# Nano-CC-EL_0v6_2_ENP252-17.net
KiCad netlist of a schematic drawn in EAGLE
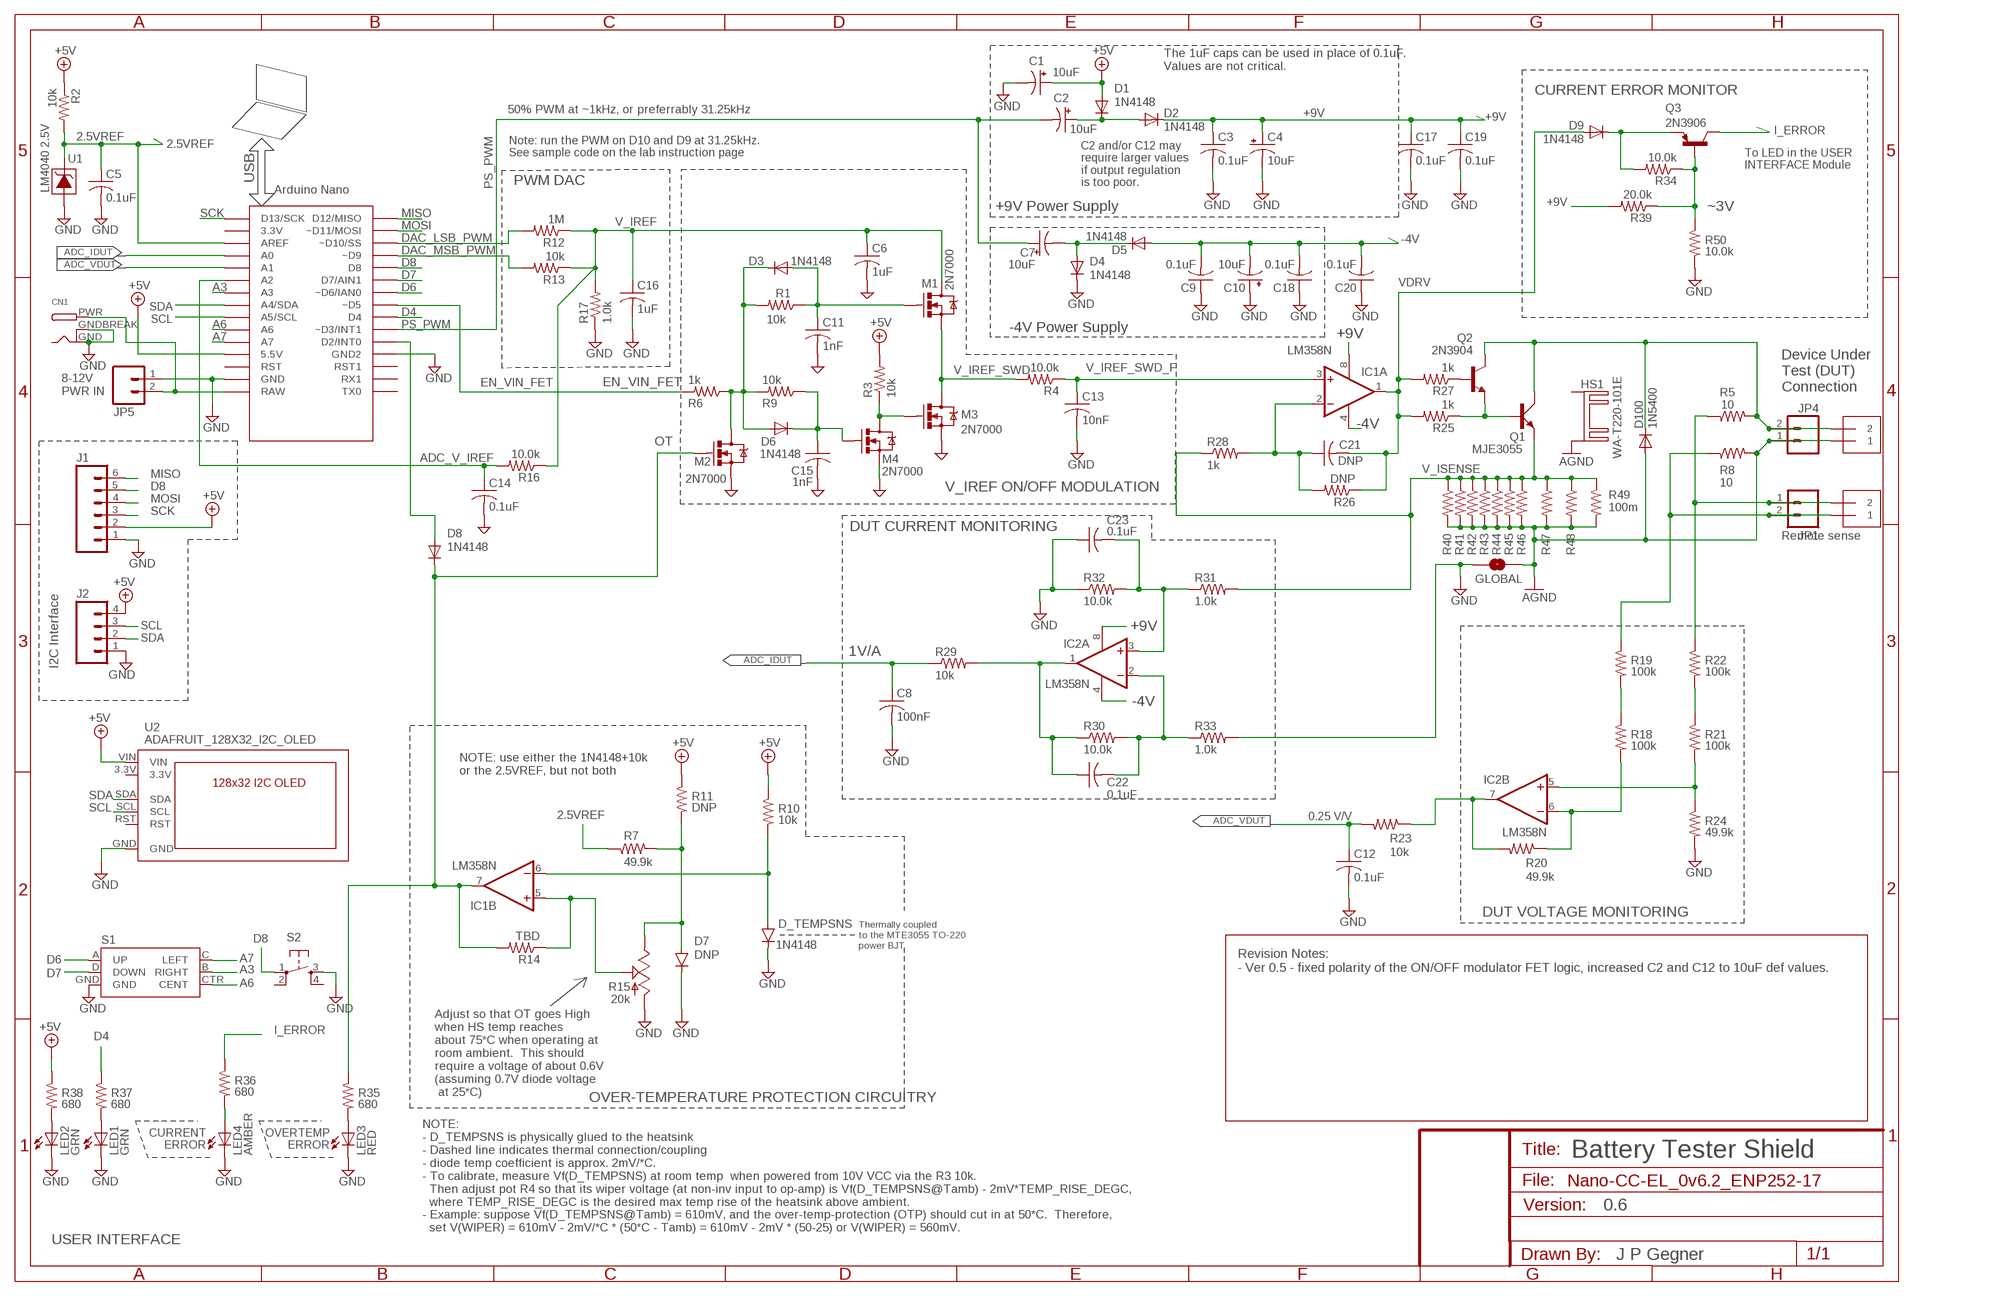
[diagram p0: schematic, sheet 1]

(export (version "E")
  (design (tool "Eeschema 10.0.6"))
  (components
    (comp (ref "C1")
      (value "10uF")
      (footprint "eagle-import:E5-5")
      (libsource (lib "eagle-import") (part "CPOL-USE5-5"))
    )
    (comp (ref "C2")
      (value "10uF")
      (footprint "eagle-import:E5-5")
      (libsource (lib "eagle-import") (part "CPOL-USE5-5"))
    )
    (comp (ref "C3")
      (value "0.1uF")
      (footprint "eagle-import:C025-025X050")
      (libsource (lib "eagle-import") (part "C-US025-025X050"))
    )
    (comp (ref "C4")
      (value "10uF")
      (footprint "eagle-import:E5-5")
      (libsource (lib "eagle-import") (part "CPOL-USE5-5"))
    )
    (comp (ref "C5")
      (value "0.1uF")
      (footprint "eagle-import:C025-025X050")
      (libsource (lib "eagle-import") (part "C-US025-025X050"))
    )
    (comp (ref "C6")
      (value "1uF")
      (footprint "eagle-import:C025-025X050")
      (libsource (lib "eagle-import") (part "C-US025-025X050"))
    )
    (comp (ref "C7")
      (value "10uF")
      (footprint "eagle-import:E5-5")
      (libsource (lib "eagle-import") (part "CPOL-USE5-5"))
    )
    (comp (ref "C8")
      (value "100nF")
      (footprint "eagle-import:C025-024X044")
      (libsource (lib "eagle-import") (part "C-US025-024X044"))
    )
    (comp (ref "C9")
      (value "0.1uF")
      (footprint "eagle-import:C025-025X050")
      (libsource (lib "eagle-import") (part "C-US025-025X050"))
    )
    (comp (ref "C10")
      (value "10uF")
      (footprint "eagle-import:E5-5")
      (libsource (lib "eagle-import") (part "CPOL-USE5-5"))
    )
    (comp (ref "C11")
      (value "1nF")
      (footprint "eagle-import:C025-025X050")
      (libsource (lib "eagle-import") (part "C-US025-025X050"))
    )
    (comp (ref "C12")
      (value "0.1uF")
      (footprint "eagle-import:C025-025X050")
      (libsource (lib "eagle-import") (part "C-US025-025X050"))
    )
    (comp (ref "C13")
      (value "10nF")
      (footprint "eagle-import:C025-025X050")
      (libsource (lib "eagle-import") (part "C-US025-025X050"))
    )
    (comp (ref "C14")
      (value "0.1uF")
      (footprint "eagle-import:C025-025X050")
      (libsource (lib "eagle-import") (part "C-US025-025X050"))
    )
    (comp (ref "C15")
      (value "1nF")
      (footprint "eagle-import:C025-025X050")
      (libsource (lib "eagle-import") (part "C-US025-025X050"))
    )
    (comp (ref "C16")
      (value "1uF")
      (footprint "eagle-import:C025-025X050")
      (libsource (lib "eagle-import") (part "C-US025-025X050"))
    )
    (comp (ref "C17")
      (value "0.1uF")
      (footprint "eagle-import:C025-025X050")
      (libsource (lib "eagle-import") (part "C-US025-025X050"))
    )
    (comp (ref "C18")
      (value "0.1uF")
      (footprint "eagle-import:C025-025X050")
      (libsource (lib "eagle-import") (part "C-US025-025X050"))
    )
    (comp (ref "C19")
      (value "0.1uF")
      (footprint "eagle-import:C025-025X050")
      (libsource (lib "eagle-import") (part "C-US025-025X050"))
    )
    (comp (ref "C20")
      (value "0.1uF")
      (footprint "eagle-import:C025-025X050")
      (libsource (lib "eagle-import") (part "C-US025-025X050"))
    )
    (comp (ref "C21")
      (value "DNP")
      (footprint "eagle-import:C025-025X050")
      (libsource (lib "eagle-import") (part "C-US025-025X050"))
    )
    (comp (ref "C22")
      (value "0.1uF")
      (footprint "eagle-import:C025-025X050")
      (libsource (lib "eagle-import") (part "C-US025-025X050"))
    )
    (comp (ref "C23")
      (value "0.1uF")
      (footprint "eagle-import:C025-025X050")
      (libsource (lib "eagle-import") (part "C-US025-025X050"))
    )
    (comp (ref "CN1")
      (value "DCBARRELPTH")
      (footprint "eagle-import:DCJACK_2MM_PTH")
      (libsource (lib "eagle-import") (part "DCBARRELPTH"))
    )
    (comp (ref "D1")
      (value "1N4148")
      (footprint "eagle-import:0207_2V-D")
      (libsource (lib "eagle-import") (part "1N4148"))
    )
    (comp (ref "D2")
      (value "1N4148")
      (footprint "eagle-import:0207_2V-D")
      (libsource (lib "eagle-import") (part "1N4148"))
    )
    (comp (ref "D3")
      (value "1N4148")
      (footprint "eagle-import:0207_2V-D")
      (libsource (lib "eagle-import") (part "1N4148"))
    )
    (comp (ref "D4")
      (value "1N4148")
      (footprint "eagle-import:0207_2V-D")
      (libsource (lib "eagle-import") (part "1N4148"))
    )
    (comp (ref "D5")
      (value "1N4148")
      (footprint "eagle-import:0207_2V-D")
      (libsource (lib "eagle-import") (part "1N4148"))
    )
    (comp (ref "D6")
      (value "1N4148")
      (footprint "eagle-import:0207_2V-D")
      (libsource (lib "eagle-import") (part "1N4148"))
    )
    (comp (ref "D7")
      (value "DNP")
      (footprint "eagle-import:0207_2V-D")
      (libsource (lib "eagle-import") (part "ideal_elements_1N4148"))
    )
    (comp (ref "D8")
      (value "1N4148")
      (footprint "eagle-import:0207_2V-D")
      (libsource (lib "eagle-import") (part "1N4148"))
    )
    (comp (ref "D9")
      (value "1N4148")
      (footprint "eagle-import:0207_2V-D")
      (libsource (lib "eagle-import") (part "1N4148"))
    )
    (comp (ref "D100")
      (value "1N5400")
      (footprint "eagle-import:DO201-15")
      (libsource (lib "eagle-import") (part "1N5400"))
    )
    (comp (ref "D_TEMPSNS")
      (value "1N4148")
      (footprint "eagle-import:0207_2V-D")
      (libsource (lib "eagle-import") (part "ideal_elements_1N4148"))
    )
    (comp (ref "GLOBAL")
      (value "JUMPER-PAD-2-NC_BY_TRACENO_SILK")
      (footprint "eagle-import:PAD-JUMPER-2-NC_BY_TRACE_NO_SILK")
      (libsource (lib "eagle-import") (part "JUMPER-PAD-2-NC_BY_TRACENO_SILK"))
    )
    (comp (ref "HS1")
      (value "WA-T220-101E")
      (footprint "eagle-import:WX-T220-101E")
      (libsource (lib "eagle-import") (part "WA-T220-101E"))
    )
    (comp (ref "IC1")
      (value "LM358N")
      (footprint "eagle-import:DIL08")
      (libsource (lib "eagle-import") (part "LM358N"))
    )
    (comp (ref "IC2")
      (value "LM358N")
      (footprint "eagle-import:DIL08")
      (libsource (lib "eagle-import") (part "LM358N"))
    )
    (comp (ref "J1")
      (value "M06POLAR")
      (footprint "eagle-import:MOLEX-1X6")
      (libsource (lib "eagle-import") (part "M06POLAR"))
    )
    (comp (ref "J2")
      (value "M04LOCK_LONGPADS")
      (footprint "eagle-import:1X04_LOCK_LONGPADS")
      (libsource (lib "eagle-import") (part "M04LOCK_LONGPADS"))
    )
    (comp (ref "JP1")
      (value "M02PTH")
      (footprint "eagle-import:1X02")
      (libsource (lib "eagle-import") (part "M02PTH"))
    )
    (comp (ref "JP2")
      (value "1X2-3.5MM")
      (footprint "eagle-import:1X2-3.5MM")
      (libsource (lib "eagle-import") (part "1X2-3.5MM"))
    )
    (comp (ref "JP3")
      (value "1X2-3.5MM")
      (footprint "eagle-import:1X2-3.5MM")
      (libsource (lib "eagle-import") (part "1X2-3.5MM"))
    )
    (comp (ref "JP4")
      (value "M02PTH")
      (footprint "eagle-import:1X02")
      (libsource (lib "eagle-import") (part "M02PTH"))
    )
    (comp (ref "JP5")
      (value "M02PTH")
      (footprint "eagle-import:1X02")
      (libsource (lib "eagle-import") (part "M02PTH"))
    )
    (comp (ref "LED1")
      (value "GRN")
      (footprint "eagle-import:LED3MM-NS")
      (libsource (lib "eagle-import") (part "LED-3MM-NO_SILK"))
    )
    (comp (ref "LED2")
      (value "GRN")
      (footprint "eagle-import:LED3MM-NS")
      (libsource (lib "eagle-import") (part "LED-3MM-NO_SILK"))
    )
    (comp (ref "LED3")
      (value "RED")
      (footprint "eagle-import:LED3MM-NS")
      (libsource (lib "eagle-import") (part "LED-3MM-NO_SILK"))
    )
    (comp (ref "LED4")
      (value "AMBER")
      (footprint "eagle-import:LED3MM-NS")
      (libsource (lib "eagle-import") (part "LED-3MM-NO_SILK"))
    )
    (comp (ref "M1")
      (value "2N7000")
      (footprint "eagle-import:TO-92")
      (libsource (lib "eagle-import") (part "MOSFET-NCHANNEL2N7000"))
    )
    (comp (ref "M2")
      (value "2N7000")
      (footprint "eagle-import:TO-92")
      (libsource (lib "eagle-import") (part "MOSFET-NCHANNEL2N7000"))
    )
    (comp (ref "M3")
      (value "2N7000")
      (footprint "eagle-import:TO-92")
      (libsource (lib "eagle-import") (part "MOSFET-NCHANNEL2N7000"))
    )
    (comp (ref "M4")
      (value "2N7000")
      (footprint "eagle-import:TO-92")
      (libsource (lib "eagle-import") (part "MOSFET-NCHANNEL2N7000"))
    )
    (comp (ref "Q1")
      (value "MJE3055")
      (footprint "eagle-import:TO220AV")
      (libsource (lib "eagle-import") (part "MJE3055"))
    )
    (comp (ref "Q2")
      (value "2N3904")
      (footprint "eagle-import:TO92")
      (libsource (lib "eagle-import") (part "2N3904"))
    )
    (comp (ref "Q3")
      (value "2N3906")
      (footprint "eagle-import:TO92")
      (libsource (lib "eagle-import") (part "2N3906"))
    )
    (comp (ref "R1")
      (value "10k")
      (footprint "eagle-import:0204_7")
      (libsource (lib "eagle-import") (part "R-US_0204/7"))
    )
    (comp (ref "R2")
      (value "10k")
      (footprint "eagle-import:0204_7")
      (libsource (lib "eagle-import") (part "R-US_0204/7"))
    )
    (comp (ref "R3")
      (value "10k")
      (footprint "eagle-import:0204_7")
      (libsource (lib "eagle-import") (part "R-US_0204/7"))
    )
    (comp (ref "R4")
      (value "10.0k")
      (footprint "eagle-import:0204V")
      (libsource (lib "eagle-import") (part "R-US_0204/2V"))
    )
    (comp (ref "R5")
      (value "10")
      (footprint "eagle-import:0204V")
      (libsource (lib "eagle-import") (part "R-US_0204/2V"))
    )
    (comp (ref "R6")
      (value "1k")
      (footprint "eagle-import:0204V")
      (libsource (lib "eagle-import") (part "R-US_0204/2V"))
    )
    (comp (ref "R7")
      (value "49.9k")
      (footprint "eagle-import:0204_7")
      (libsource (lib "eagle-import") (part "R-US_0204/7"))
    )
    (comp (ref "R8")
      (value "10")
      (footprint "eagle-import:0204V")
      (libsource (lib "eagle-import") (part "R-US_0204/2V"))
    )
    (comp (ref "R9")
      (value "10k")
      (footprint "eagle-import:0204_7")
      (libsource (lib "eagle-import") (part "R-US_0204/7"))
    )
    (comp (ref "R10")
      (value "10k")
      (footprint "eagle-import:0204_7")
      (libsource (lib "eagle-import") (part "R-US_0204/7"))
    )
    (comp (ref "R11")
      (value "DNP")
      (footprint "eagle-import:0204_7")
      (libsource (lib "eagle-import") (part "R-US_0204/7"))
    )
    (comp (ref "R12")
      (value "1M")
      (footprint "eagle-import:0204_7")
      (libsource (lib "eagle-import") (part "R-US_0204/7"))
    )
    (comp (ref "R13")
      (value "10k")
      (footprint "eagle-import:0204_7")
      (libsource (lib "eagle-import") (part "R-US_0204/7"))
    )
    (comp (ref "R14")
      (value "TBD")
      (footprint "eagle-import:0204_7")
      (libsource (lib "eagle-import") (part "R-US_0204/7"))
    )
    (comp (ref "R15")
      (value "20k")
      (footprint "eagle-import:B64Y")
      (libsource (lib "eagle-import") (part "TRIM_US-B64Y"))
    )
    (comp (ref "R16")
      (value "10.0k")
      (footprint "eagle-import:0204_7")
      (libsource (lib "eagle-import") (part "R-US_0204/7"))
    )
    (comp (ref "R17")
      (value "1.0k")
      (footprint "eagle-import:0204_7")
      (libsource (lib "eagle-import") (part "R-US_0204/7"))
    )
    (comp (ref "R18")
      (value "100k")
      (footprint "eagle-import:0204_7")
      (libsource (lib "eagle-import") (part "R-US_0204/7"))
    )
    (comp (ref "R19")
      (value "100k")
      (footprint "eagle-import:0204_7")
      (libsource (lib "eagle-import") (part "R-US_0204/7"))
    )
    (comp (ref "R20")
      (value "49.9k")
      (footprint "eagle-import:0204V")
      (libsource (lib "eagle-import") (part "R-US_0204/2V"))
    )
    (comp (ref "R21")
      (value "100k")
      (footprint "eagle-import:0204_7")
      (libsource (lib "eagle-import") (part "R-US_0204/7"))
    )
    (comp (ref "R22")
      (value "100k")
      (footprint "eagle-import:0204_7")
      (libsource (lib "eagle-import") (part "R-US_0204/7"))
    )
    (comp (ref "R23")
      (value "10k")
      (footprint "eagle-import:0204_7")
      (libsource (lib "eagle-import") (part "R-US_0204/7"))
    )
    (comp (ref "R24")
      (value "49.9k")
      (footprint "eagle-import:0204_7")
      (libsource (lib "eagle-import") (part "R-US_0204/7"))
    )
    (comp (ref "R25")
      (value "1k")
      (footprint "eagle-import:0204_7")
      (libsource (lib "eagle-import") (part "R-US_0204/7"))
    )
    (comp (ref "R26")
      (value "DNP")
      (footprint "eagle-import:0204V")
      (libsource (lib "eagle-import") (part "R-US_0204/2V"))
    )
    (comp (ref "R27")
      (value "1k")
      (footprint "eagle-import:0204_7")
      (libsource (lib "eagle-import") (part "R-US_0204/7"))
    )
    (comp (ref "R28")
      (value "1k")
      (footprint "eagle-import:0204_7")
      (libsource (lib "eagle-import") (part "R-US_0204/7"))
    )
    (comp (ref "R29")
      (value "10k")
      (footprint "eagle-import:0204_7")
      (libsource (lib "eagle-import") (part "R-US_0204/7"))
    )
    (comp (ref "R30")
      (value "10.0k")
      (footprint "eagle-import:0204V")
      (libsource (lib "eagle-import") (part "R-US_0204/2V"))
    )
    (comp (ref "R31")
      (value "1.0k")
      (footprint "eagle-import:0204_7")
      (libsource (lib "eagle-import") (part "R-US_0204/7"))
    )
    (comp (ref "R32")
      (value "10.0k")
      (footprint "eagle-import:0204_7")
      (libsource (lib "eagle-import") (part "R-US_0204/7"))
    )
    (comp (ref "R33")
      (value "1.0k")
      (footprint "eagle-import:0204_7")
      (libsource (lib "eagle-import") (part "R-US_0204/7"))
    )
    (comp (ref "R34")
      (value "10.0k")
      (footprint "eagle-import:0204_7")
      (libsource (lib "eagle-import") (part "R-US_0204/7"))
    )
    (comp (ref "R35")
      (value "680")
      (footprint "eagle-import:0204_7")
      (libsource (lib "eagle-import") (part "R-US_0204/7"))
    )
    (comp (ref "R36")
      (value "680")
      (footprint "eagle-import:0204_7")
      (libsource (lib "eagle-import") (part "R-US_0204/7"))
    )
    (comp (ref "R37")
      (value "680")
      (footprint "eagle-import:0207_15")
      (libsource (lib "eagle-import") (part "R-US_0207/15"))
    )
    (comp (ref "R38")
      (value "680")
      (footprint "eagle-import:0204_7")
      (libsource (lib "eagle-import") (part "R-US_0204/7"))
    )
    (comp (ref "R39")
      (value "20.0k")
      (footprint "eagle-import:0204_7")
      (libsource (lib "eagle-import") (part "R-US_0204/7"))
    )
    (comp (ref "R40")
      (value "100m")
      (footprint "eagle-import:0204_7")
      (libsource (lib "eagle-import") (part "R-US_0204/7"))
    )
    (comp (ref "R41")
      (value "100m")
      (footprint "eagle-import:0204_7")
      (libsource (lib "eagle-import") (part "R-US_0204/7"))
    )
    (comp (ref "R42")
      (value "100m")
      (footprint "eagle-import:0204_7")
      (libsource (lib "eagle-import") (part "R-US_0204/7"))
    )
    (comp (ref "R43")
      (value "100m")
      (footprint "eagle-import:0204_7")
      (libsource (lib "eagle-import") (part "R-US_0204/7"))
    )
    (comp (ref "R44")
      (value "100m")
      (footprint "eagle-import:0204_7")
      (libsource (lib "eagle-import") (part "R-US_0204/7"))
    )
    (comp (ref "R45")
      (value "100m")
      (footprint "eagle-import:0204_7")
      (libsource (lib "eagle-import") (part "R-US_0204/7"))
    )
    (comp (ref "R46")
      (value "100m")
      (footprint "eagle-import:0204_7")
      (libsource (lib "eagle-import") (part "R-US_0204/7"))
    )
    (comp (ref "R47")
      (value "100m")
      (footprint "eagle-import:0204_7")
      (libsource (lib "eagle-import") (part "R-US_0204/7"))
    )
    (comp (ref "R48")
      (value "100m")
      (footprint "eagle-import:0204_7")
      (libsource (lib "eagle-import") (part "R-US_0204/7"))
    )
    (comp (ref "R49")
      (value "100m")
      (footprint "eagle-import:0204_7")
      (libsource (lib "eagle-import") (part "R-US_0204/7"))
    )
    (comp (ref "R50")
      (value "10.0k")
      (footprint "eagle-import:0204_7")
      (libsource (lib "eagle-import") (part "R-US_0204/7"))
    )
    (comp (ref "S1")
      (value "JOYSTICK_MINI")
      (footprint "eagle-import:JOYSTICK_MINI")
      (libsource (lib "eagle-import") (part "JOYSTICK_MINI"))
    )
    (comp (ref "S2")
      (value "E-SWITCH_TL1105L-F250-Q")
      (footprint "eagle-import:OMRON_B3F-1XX-JPGMOD")
      (libsource (lib "eagle-import") (part "E-SWITCH_TL1105L-F250-Q"))
    )
    (comp (ref "U$1")
      (value "NANO")
      (footprint "eagle-import:NANO")
      (libsource (lib "eagle-import") (part "NANO"))
    )
    (comp (ref "U1")
      (value "LM4040 2.5V")
      (footprint "eagle-import:TO92")
      (libsource (lib "eagle-import") (part "LM4040TO92"))
    )
    (comp (ref "U2")
      (value "ADAFRUIT_128X32_I2C_OLED")
      (footprint "eagle-import:ADAFRUIT_128X32_I2C_OLED")
      (libsource (lib "eagle-import") (part "ADAFRUIT_128X32_I2C_OLED"))
    )
  )
  (nets
    (net (code "1") (name "+5V") (class "Default")
      (node (ref "C1") (pin "+") (pinfunction "+_+") (pintype "passive"))
      (node (ref "D1") (pin "A") (pinfunction "A_A") (pintype "passive"))
      (node (ref "J1") (pin "2") (pinfunction "2_2") (pintype "passive"))
      (node (ref "J2") (pin "4") (pinfunction "4_4") (pintype "passive"))
      (node (ref "R10") (pin "1") (pinfunction "1_1") (pintype "passive"))
      (node (ref "R11") (pin "1") (pinfunction "1_1") (pintype "passive"))
      (node (ref "R2") (pin "1") (pinfunction "1_1") (pintype "passive"))
      (node (ref "R3") (pin "2") (pinfunction "2_2") (pintype "passive"))
      (node (ref "R38") (pin "1") (pinfunction "1_1") (pintype "passive"))
      (node (ref "U$1") (pin "5V") (pinfunction "5.5V_5V") (pintype "bidirectional"))
      (node (ref "U2") (pin "VIN") (pinfunction "VIN_VIN") (pintype "power_in"))
    )
    (net (code "2") (name "/+9V") (class "Default")
      (node (ref "C17") (pin "1") (pinfunction "1_1") (pintype "passive"))
      (node (ref "C19") (pin "1") (pinfunction "1_1") (pintype "passive"))
      (node (ref "C3") (pin "1") (pinfunction "1_1") (pintype "passive"))
      (node (ref "C4") (pin "+") (pinfunction "+_+") (pintype "passive"))
      (node (ref "D2") (pin "K") (pinfunction "C_K") (pintype "passive"))
      (node (ref "IC1") (pin "8") (pinfunction "V+_8") (pintype "power_in"))
      (node (ref "IC2") (pin "8") (pinfunction "V+_8") (pintype "power_in"))
      (node (ref "R39") (pin "2") (pinfunction "2_2") (pintype "passive"))
    )
    (net (code "3") (name "/-4V") (class "Default")
      (node (ref "C10") (pin "-") (pinfunction "-_-") (pintype "passive"))
      (node (ref "C18") (pin "2") (pinfunction "2_2") (pintype "passive"))
      (node (ref "C20") (pin "2") (pinfunction "2_2") (pintype "passive"))
      (node (ref "C9") (pin "2") (pinfunction "2_2") (pintype "passive"))
      (node (ref "D5") (pin "A") (pinfunction "A_A") (pintype "passive"))
      (node (ref "IC1") (pin "4") (pinfunction "V-_4") (pintype "power_in"))
      (node (ref "IC2") (pin "4") (pinfunction "V-_4") (pintype "power_in"))
    )
    (net (code "4") (name "/2.5VREF") (class "Default")
      (node (ref "C5") (pin "1") (pinfunction "1_1") (pintype "passive"))
      (node (ref "R2") (pin "2") (pinfunction "2_2") (pintype "passive"))
      (node (ref "R7") (pin "1") (pinfunction "1_1") (pintype "passive"))
      (node (ref "U$1") (pin "AREF") (pinfunction "AREF_AREF") (pintype "bidirectional"))
      (node (ref "U1") (pin "2") (pinfunction "CATHODE_2") (pintype "passive"))
    )
    (net (code "5") (name "/3.3V") (class "Default")
      (node (ref "U2") (pin "3.3V") (pinfunction "3.3V_3.3V") (pintype "power_in"))
    )
    (net (code "6") (name "/A3") (class "Default")
      (node (ref "S1") (pin "B") (pinfunction "RIGHT_B") (pintype "bidirectional"))
      (node (ref "U$1") (pin "A3") (pinfunction "A3_A3") (pintype "bidirectional"))
    )
    (net (code "7") (name "/A6") (class "Default")
      (node (ref "S1") (pin "CTR") (pinfunction "CENT_CTR") (pintype "bidirectional"))
      (node (ref "U$1") (pin "A6") (pinfunction "A6_A6") (pintype "bidirectional"))
    )
    (net (code "8") (name "/A7") (class "Default")
      (node (ref "S1") (pin "C") (pinfunction "LEFT_C") (pintype "bidirectional"))
      (node (ref "U$1") (pin "A7") (pinfunction "A7_A7") (pintype "bidirectional"))
    )
    (net (code "9") (name "/ADC_IDUT") (class "Default")
      (node (ref "C8") (pin "1") (pinfunction "1_1") (pintype "passive"))
      (node (ref "R29") (pin "1") (pinfunction "1_1") (pintype "passive"))
      (node (ref "U$1") (pin "A0") (pinfunction "A0_A0") (pintype "bidirectional"))
    )
    (net (code "10") (name "/ADC_VDUT") (class "Default")
      (node (ref "C12") (pin "1") (pinfunction "1_1") (pintype "passive"))
      (node (ref "R23") (pin "2") (pinfunction "2_2") (pintype "passive"))
      (node (ref "U$1") (pin "A1") (pinfunction "A1_A1") (pintype "bidirectional"))
    )
    (net (code "11") (name "/ADC_V_IREF") (class "Default")
      (node (ref "C14") (pin "1") (pinfunction "1_1") (pintype "passive"))
      (node (ref "R16") (pin "2") (pinfunction "2_2") (pintype "passive"))
      (node (ref "U$1") (pin "A2") (pinfunction "A2_A2") (pintype "bidirectional"))
    )
    (net (code "12") (name "/D4") (class "Default")
      (node (ref "R37") (pin "1") (pinfunction "1_1") (pintype "passive"))
      (node (ref "U$1") (pin "D4") (pinfunction "D4_D4") (pintype "bidirectional"))
    )
    (net (code "13") (name "/D6") (class "Default")
      (node (ref "S1") (pin "A") (pinfunction "UP_A") (pintype "bidirectional"))
      (node (ref "U$1") (pin "D6") (pinfunction "~{D6/IAN0}_D6") (pintype "bidirectional"))
    )
    (net (code "14") (name "/D7") (class "Default")
      (node (ref "S1") (pin "D") (pinfunction "DOWN_D") (pintype "bidirectional"))
      (node (ref "U$1") (pin "D7") (pinfunction "D7/AIN1_D7") (pintype "bidirectional"))
    )
    (net (code "15") (name "/D8") (class "Default")
      (node (ref "J1") (pin "5") (pinfunction "5_5") (pintype "passive"))
      (node (ref "S2") (pin "1") (pinfunction "P_1") (pintype "passive"))
      (node (ref "U$1") (pin "D8") (pinfunction "D8_D8") (pintype "bidirectional"))
    )
    (net (code "16") (name "/DAC_LSB_PWM") (class "Default")
      (node (ref "R12") (pin "2") (pinfunction "2_2") (pintype "passive"))
      (node (ref "U$1") (pin "D10") (pinfunction "~{D10/SS}_D10") (pintype "bidirectional"))
    )
    (net (code "17") (name "/DAC_MSB_PWM") (class "Default")
      (node (ref "R13") (pin "2") (pinfunction "2_2") (pintype "passive"))
      (node (ref "U$1") (pin "D9") (pinfunction "~{D9}_D9") (pintype "bidirectional"))
    )
    (net (code "18") (name "/EN_VIN_FET") (class "Default")
      (node (ref "R6") (pin "2") (pinfunction "2_2") (pintype "passive"))
      (node (ref "U$1") (pin "D5") (pinfunction "~{D5}_D5") (pintype "bidirectional"))
    )
    (net (code "19") (name "/I_ERROR") (class "Default")
      (node (ref "Q3") (pin "1") (pinfunction "C_1") (pintype "passive"))
      (node (ref "R36") (pin "1") (pinfunction "1_1") (pintype "passive"))
    )
    (net (code "20") (name "/MISO") (class "Default")
      (node (ref "J1") (pin "6") (pinfunction "6_6") (pintype "passive"))
      (node (ref "U$1") (pin "D12") (pinfunction "D12/MISO_D12") (pintype "bidirectional"))
    )
    (net (code "21") (name "/MOSI") (class "Default")
      (node (ref "J1") (pin "4") (pinfunction "4_4") (pintype "passive"))
      (node (ref "U$1") (pin "D11") (pinfunction "~{D11/MOSI}_D11") (pintype "bidirectional"))
    )
    (net (code "22") (name "/OT") (class "Default")
      (node (ref "D8") (pin "K") (pinfunction "C_K") (pintype "passive"))
      (node (ref "IC1") (pin "7") (pinfunction "OUT_7") (pintype "output"))
      (node (ref "M2") (pin "2") (pinfunction "G_2") (pintype "passive"))
      (node (ref "R14") (pin "2") (pinfunction "2_2") (pintype "passive"))
      (node (ref "R35") (pin "1") (pinfunction "1_1") (pintype "passive"))
    )
    (net (code "23") (name "/PS_PWM") (class "Default")
      (node (ref "C2") (pin "-") (pinfunction "-_-") (pintype "passive"))
      (node (ref "C7") (pin "+") (pinfunction "+_+") (pintype "passive"))
      (node (ref "U$1") (pin "D3") (pinfunction "~{D3/INT1}_D3") (pintype "bidirectional"))
    )
    (net (code "24") (name "/SCK") (class "Default")
      (node (ref "J1") (pin "3") (pinfunction "3_3") (pintype "passive"))
      (node (ref "U$1") (pin "D13") (pinfunction "D13/SCK_D13") (pintype "bidirectional"))
    )
    (net (code "25") (name "/SCL") (class "Default")
      (node (ref "J2") (pin "3") (pinfunction "3_3") (pintype "passive"))
      (node (ref "U$1") (pin "A5") (pinfunction "A5/SCL_A5") (pintype "bidirectional"))
      (node (ref "U2") (pin "SCL") (pinfunction "SCL_SCL") (pintype "bidirectional"))
    )
    (net (code "26") (name "/SDA") (class "Default")
      (node (ref "J2") (pin "2") (pinfunction "2_2") (pintype "passive"))
      (node (ref "U$1") (pin "A4") (pinfunction "A4/SDA_A4") (pintype "bidirectional"))
      (node (ref "U2") (pin "SDA") (pinfunction "SDA_SDA") (pintype "bidirectional"))
    )
    (net (code "27") (name "/VDRV") (class "Default")
      (node (ref "C21") (pin "2") (pinfunction "2_2") (pintype "passive"))
      (node (ref "D9") (pin "A") (pinfunction "A_A") (pintype "passive"))
      (node (ref "IC1") (pin "1") (pinfunction "OUT_1") (pintype "output"))
      (node (ref "R25") (pin "2") (pinfunction "2_2") (pintype "passive"))
      (node (ref "R26") (pin "1") (pinfunction "1_1") (pintype "passive"))
      (node (ref "R27") (pin "2") (pinfunction "2_2") (pintype "passive"))
    )
    (net (code "28") (name "/V_IREF") (class "Default")
      (node (ref "C16") (pin "1") (pinfunction "1_1") (pintype "passive"))
      (node (ref "C6") (pin "1") (pinfunction "1_1") (pintype "passive"))
      (node (ref "M1") (pin "3") (pinfunction "D_3") (pintype "passive"))
      (node (ref "R12") (pin "1") (pinfunction "1_1") (pintype "passive"))
      (node (ref "R13") (pin "1") (pinfunction "1_1") (pintype "passive"))
      (node (ref "R16") (pin "1") (pinfunction "1_1") (pintype "passive"))
      (node (ref "R17") (pin "2") (pinfunction "2_2") (pintype "passive"))
    )
    (net (code "29") (name "/V_IREF_SWD") (class "Default")
      (node (ref "M1") (pin "1") (pinfunction "S_1") (pintype "passive"))
      (node (ref "M3") (pin "3") (pinfunction "D_3") (pintype "passive"))
      (node (ref "R4") (pin "2") (pinfunction "2_2") (pintype "passive"))
    )
    (net (code "30") (name "/V_IREF_SWD_F") (class "Default")
      (node (ref "C13") (pin "1") (pinfunction "1_1") (pintype "passive"))
      (node (ref "IC1") (pin "3") (pinfunction "+IN_3") (pintype "input"))
      (node (ref "R4") (pin "1") (pinfunction "1_1") (pintype "passive"))
    )
    (net (code "31") (name "/V_ISENSE") (class "Default")
      (node (ref "Q1") (pin "E") (pinfunction "E_E") (pintype "passive"))
      (node (ref "R28") (pin "1") (pinfunction "1_1") (pintype "passive"))
      (node (ref "R31") (pin "2") (pinfunction "2_2") (pintype "passive"))
      (node (ref "R40") (pin "1") (pinfunction "1_1") (pintype "passive"))
      (node (ref "R41") (pin "1") (pinfunction "1_1") (pintype "passive"))
      (node (ref "R42") (pin "1") (pinfunction "1_1") (pintype "passive"))
      (node (ref "R43") (pin "1") (pinfunction "1_1") (pintype "passive"))
      (node (ref "R44") (pin "1") (pinfunction "1_1") (pintype "passive"))
      (node (ref "R45") (pin "1") (pinfunction "1_1") (pintype "passive"))
      (node (ref "R46") (pin "1") (pinfunction "1_1") (pintype "passive"))
      (node (ref "R47") (pin "1") (pinfunction "1_1") (pintype "passive"))
      (node (ref "R48") (pin "1") (pinfunction "1_1") (pintype "passive"))
      (node (ref "R49") (pin "1") (pinfunction "1_1") (pintype "passive"))
    )
    (net (code "32") (name "AGND") (class "Default")
      (node (ref "D100") (pin "A") (pinfunction "A_A") (pintype "passive"))
      (node (ref "GLOBAL") (pin "2") (pinfunction "2_2") (pintype "passive"))
      (node (ref "HS1") (pin "K2") (pinfunction "K_K2") (pintype "passive"))
      (node (ref "JP3") (pin "1") (pinfunction "1_1") (pintype "passive"))
      (node (ref "JP4") (pin "1") (pinfunction "1_1") (pintype "passive"))
      (node (ref "R40") (pin "2") (pinfunction "2_2") (pintype "passive"))
      (node (ref "R41") (pin "2") (pinfunction "2_2") (pintype "passive"))
      (node (ref "R42") (pin "2") (pinfunction "2_2") (pintype "passive"))
      (node (ref "R43") (pin "2") (pinfunction "2_2") (pintype "passive"))
      (node (ref "R44") (pin "2") (pinfunction "2_2") (pintype "passive"))
      (node (ref "R45") (pin "2") (pinfunction "2_2") (pintype "passive"))
      (node (ref "R46") (pin "2") (pinfunction "2_2") (pintype "passive"))
      (node (ref "R47") (pin "2") (pinfunction "2_2") (pintype "passive"))
      (node (ref "R48") (pin "2") (pinfunction "2_2") (pintype "passive"))
      (node (ref "R49") (pin "2") (pinfunction "2_2") (pintype "passive"))
      (node (ref "R8") (pin "2") (pinfunction "2_2") (pintype "passive"))
    )
    (net (code "33") (name "GND") (class "Default")
      (node (ref "C1") (pin "-") (pinfunction "-_-") (pintype "passive"))
      (node (ref "C10") (pin "+") (pinfunction "+_+") (pintype "passive"))
      (node (ref "C11") (pin "2") (pinfunction "2_2") (pintype "passive"))
      (node (ref "C12") (pin "2") (pinfunction "2_2") (pintype "passive"))
      (node (ref "C13") (pin "2") (pinfunction "2_2") (pintype "passive"))
      (node (ref "C14") (pin "2") (pinfunction "2_2") (pintype "passive"))
      (node (ref "C15") (pin "2") (pinfunction "2_2") (pintype "passive"))
      (node (ref "C16") (pin "2") (pinfunction "2_2") (pintype "passive"))
      (node (ref "C17") (pin "2") (pinfunction "2_2") (pintype "passive"))
      (node (ref "C18") (pin "1") (pinfunction "1_1") (pintype "passive"))
      (node (ref "C19") (pin "2") (pinfunction "2_2") (pintype "passive"))
      (node (ref "C20") (pin "1") (pinfunction "1_1") (pintype "passive"))
      (node (ref "C23") (pin "1") (pinfunction "1_1") (pintype "passive"))
      (node (ref "C3") (pin "2") (pinfunction "2_2") (pintype "passive"))
      (node (ref "C4") (pin "-") (pinfunction "-_-") (pintype "passive"))
      (node (ref "C5") (pin "2") (pinfunction "2_2") (pintype "passive"))
      (node (ref "C6") (pin "2") (pinfunction "2_2") (pintype "passive"))
      (node (ref "C8") (pin "2") (pinfunction "2_2") (pintype "passive"))
      (node (ref "C9") (pin "1") (pinfunction "1_1") (pintype "passive"))
      (node (ref "CN1") (pin "GND") (pinfunction "GND_GND") (pintype "power_in"))
      (node (ref "CN1") (pin "GNDBREAK") (pinfunction "GNDBREAK_GNDBREAK") (pintype "power_in"))
      (node (ref "D4") (pin "K") (pinfunction "C_K") (pintype "passive"))
      (node (ref "D7") (pin "K") (pinfunction "C_K") (pintype "passive"))
      (node (ref "D_TEMPSNS") (pin "K") (pinfunction "C_K") (pintype "passive"))
      (node (ref "GLOBAL") (pin "1") (pinfunction "1_1") (pintype "passive"))
      (node (ref "J1") (pin "1") (pinfunction "1_1") (pintype "passive"))
      (node (ref "J2") (pin "1") (pinfunction "1_1") (pintype "passive"))
      (node (ref "JP5") (pin "1") (pinfunction "1_1") (pintype "passive"))
      (node (ref "LED1") (pin "K") (pinfunction "C_K") (pintype "passive"))
      (node (ref "LED2") (pin "K") (pinfunction "C_K") (pintype "passive"))
      (node (ref "LED3") (pin "K") (pinfunction "C_K") (pintype "passive"))
      (node (ref "LED4") (pin "K") (pinfunction "C_K") (pintype "passive"))
      (node (ref "M2") (pin "1") (pinfunction "S_1") (pintype "passive"))
      (node (ref "M3") (pin "1") (pinfunction "S_1") (pintype "passive"))
      (node (ref "M4") (pin "1") (pinfunction "S_1") (pintype "passive"))
      (node (ref "R15") (pin "A") (pinfunction "A_A") (pintype "passive"))
      (node (ref "R17") (pin "1") (pinfunction "1_1") (pintype "passive"))
      (node (ref "R24") (pin "2") (pinfunction "2_2") (pintype "passive"))
      (node (ref "R32") (pin "1") (pinfunction "1_1") (pintype "passive"))
      (node (ref "R33") (pin "2") (pinfunction "2_2") (pintype "passive"))
      (node (ref "R50") (pin "2") (pinfunction "2_2") (pintype "passive"))
      (node (ref "S1") (pin "GND") (pinfunction "GND_GND") (pintype "bidirectional"))
      (node (ref "S2") (pin "3") (pinfunction "S_3") (pintype "passive"))
      (node (ref "U$1") (pin "GND") (pinfunction "GND_GND") (pintype "bidirectional"))
      (node (ref "U$1") (pin "GND1") (pinfunction "GND2_GND1") (pintype "bidirectional"))
      (node (ref "U1") (pin "3") (pinfunction "ANODE_3") (pintype "passive"))
      (node (ref "U2") (pin "GND") (pinfunction "GND_GND") (pintype "power_in"))
    )
    (net (code "34") (name "Net-(CN1-PadPWR)") (class "Default")
      (node (ref "CN1") (pin "PWR") (pinfunction "PWR_PWR") (pintype "power_in"))
      (node (ref "JP5") (pin "2") (pinfunction "2_2") (pintype "passive"))
      (node (ref "U$1") (pin "RAW") (pinfunction "RAW_RAW") (pintype "bidirectional"))
    )
    (net (code "35") (name "Net-(D1-C)") (class "Default")
      (node (ref "C2") (pin "+") (pinfunction "+_+") (pintype "passive"))
      (node (ref "D1") (pin "K") (pinfunction "C_K") (pintype "passive"))
      (node (ref "D2") (pin "A") (pinfunction "A_A") (pintype "passive"))
    )
    (net (code "36") (name "Net-(D3-C)") (class "Default")
      (node (ref "D3") (pin "K") (pinfunction "C_K") (pintype "passive"))
      (node (ref "D6") (pin "A") (pinfunction "A_A") (pintype "passive"))
      (node (ref "M2") (pin "3") (pinfunction "D_3") (pintype "passive"))
      (node (ref "R1") (pin "2") (pinfunction "2_2") (pintype "passive"))
      (node (ref "R6") (pin "1") (pinfunction "1_1") (pintype "passive"))
      (node (ref "R9") (pin "2") (pinfunction "2_2") (pintype "passive"))
    )
    (net (code "37") (name "Net-(D5-C)") (class "Default")
      (node (ref "C7") (pin "-") (pinfunction "-_-") (pintype "passive"))
      (node (ref "D4") (pin "A") (pinfunction "A_A") (pintype "passive"))
      (node (ref "D5") (pin "K") (pinfunction "C_K") (pintype "passive"))
    )
    (net (code "38") (name "Net-(D6-C)") (class "Default")
      (node (ref "C15") (pin "1") (pinfunction "1_1") (pintype "passive"))
      (node (ref "D6") (pin "K") (pinfunction "C_K") (pintype "passive"))
      (node (ref "M4") (pin "2") (pinfunction "G_2") (pintype "passive"))
      (node (ref "R9") (pin "1") (pinfunction "1_1") (pintype "passive"))
    )
    (net (code "39") (name "Net-(D7-PadA)") (class "Default")
      (node (ref "D7") (pin "A") (pinfunction "A_A") (pintype "passive"))
      (node (ref "R11") (pin "2") (pinfunction "2_2") (pintype "passive"))
      (node (ref "R15") (pin "E") (pinfunction "E_E") (pintype "passive"))
      (node (ref "R7") (pin "2") (pinfunction "2_2") (pintype "passive"))
    )
    (net (code "40") (name "Net-(D9-C)") (class "Default")
      (node (ref "D9") (pin "K") (pinfunction "C_K") (pintype "passive"))
      (node (ref "Q3") (pin "3") (pinfunction "E_3") (pintype "passive"))
      (node (ref "R34") (pin "2") (pinfunction "2_2") (pintype "passive"))
    )
    (net (code "41") (name "Net-(IC1A--IN)") (class "Default")
      (node (ref "C21") (pin "1") (pinfunction "1_1") (pintype "passive"))
      (node (ref "IC1") (pin "2") (pinfunction "-IN_2") (pintype "input"))
      (node (ref "R26") (pin "2") (pinfunction "2_2") (pintype "passive"))
      (node (ref "R28") (pin "2") (pinfunction "2_2") (pintype "passive"))
    )
    (net (code "42") (name "Net-(IC1B-+IN)") (class "Default")
      (node (ref "IC1") (pin "5") (pinfunction "+IN_5") (pintype "input"))
      (node (ref "R14") (pin "1") (pinfunction "1_1") (pintype "passive"))
      (node (ref "R15") (pin "S") (pinfunction "S_S") (pintype "passive"))
    )
    (net (code "43") (name "Net-(IC1B--IN)") (class "Default")
      (node (ref "D_TEMPSNS") (pin "A") (pinfunction "A_A") (pintype "passive"))
      (node (ref "IC1") (pin "6") (pinfunction "-IN_6") (pintype "input"))
      (node (ref "R10") (pin "2") (pinfunction "2_2") (pintype "passive"))
    )
    (net (code "44") (name "Net-(IC2A-+IN)") (class "Default")
      (node (ref "C23") (pin "2") (pinfunction "2_2") (pintype "passive"))
      (node (ref "IC2") (pin "3") (pinfunction "+IN_3") (pintype "input"))
      (node (ref "R31") (pin "1") (pinfunction "1_1") (pintype "passive"))
      (node (ref "R32") (pin "2") (pinfunction "2_2") (pintype "passive"))
    )
    (net (code "45") (name "Net-(IC2A--IN)") (class "Default")
      (node (ref "C22") (pin "2") (pinfunction "2_2") (pintype "passive"))
      (node (ref "IC2") (pin "2") (pinfunction "-IN_2") (pintype "input"))
      (node (ref "R30") (pin "2") (pinfunction "2_2") (pintype "passive"))
      (node (ref "R33") (pin "1") (pinfunction "1_1") (pintype "passive"))
    )
    (net (code "46") (name "Net-(IC2A-OUT)") (class "Default")
      (node (ref "C22") (pin "1") (pinfunction "1_1") (pintype "passive"))
      (node (ref "IC2") (pin "1") (pinfunction "OUT_1") (pintype "output"))
      (node (ref "R29") (pin "2") (pinfunction "2_2") (pintype "passive"))
      (node (ref "R30") (pin "1") (pinfunction "1_1") (pintype "passive"))
    )
    (net (code "47") (name "Net-(IC2B-+IN)") (class "Default")
      (node (ref "IC2") (pin "5") (pinfunction "+IN_5") (pintype "input"))
      (node (ref "R21") (pin "2") (pinfunction "2_2") (pintype "passive"))
      (node (ref "R24") (pin "1") (pinfunction "1_1") (pintype "passive"))
    )
    (net (code "48") (name "Net-(IC2B--IN)") (class "Default")
      (node (ref "IC2") (pin "6") (pinfunction "-IN_6") (pintype "input"))
      (node (ref "R18") (pin "2") (pinfunction "2_2") (pintype "passive"))
      (node (ref "R20") (pin "1") (pinfunction "1_1") (pintype "passive"))
    )
    (net (code "49") (name "Net-(IC2B-OUT)") (class "Default")
      (node (ref "IC2") (pin "7") (pinfunction "OUT_7") (pintype "output"))
      (node (ref "R20") (pin "2") (pinfunction "2_2") (pintype "passive"))
      (node (ref "R23") (pin "1") (pinfunction "1_1") (pintype "passive"))
    )
    (net (code "50") (name "Net-(JP1-Pad1)") (class "Default")
      (node (ref "JP1") (pin "1") (pinfunction "1_1") (pintype "passive"))
      (node (ref "JP2") (pin "2") (pinfunction "2_2") (pintype "passive"))
      (node (ref "R22") (pin "1") (pinfunction "1_1") (pintype "passive"))
      (node (ref "R5") (pin "1") (pinfunction "1_1") (pintype "passive"))
    )
    (net (code "51") (name "Net-(JP1-Pad2)") (class "Default")
      (node (ref "JP1") (pin "2") (pinfunction "2_2") (pintype "passive"))
      (node (ref "JP2") (pin "1") (pinfunction "1_1") (pintype "passive"))
      (node (ref "R19") (pin "1") (pinfunction "1_1") (pintype "passive"))
      (node (ref "R8") (pin "1") (pinfunction "1_1") (pintype "passive"))
    )
    (net (code "52") (name "Net-(LED1-PadA)") (class "Default")
      (node (ref "LED1") (pin "A") (pinfunction "A_A") (pintype "passive"))
      (node (ref "R37") (pin "2") (pinfunction "2_2") (pintype "passive"))
    )
    (net (code "53") (name "Net-(LED2-PadA)") (class "Default")
      (node (ref "LED2") (pin "A") (pinfunction "A_A") (pintype "passive"))
      (node (ref "R38") (pin "2") (pinfunction "2_2") (pintype "passive"))
    )
    (net (code "54") (name "Net-(LED3-PadA)") (class "Default")
      (node (ref "LED3") (pin "A") (pinfunction "A_A") (pintype "passive"))
      (node (ref "R35") (pin "2") (pinfunction "2_2") (pintype "passive"))
    )
    (net (code "55") (name "Net-(LED4-PadA)") (class "Default")
      (node (ref "LED4") (pin "A") (pinfunction "A_A") (pintype "passive"))
      (node (ref "R36") (pin "2") (pinfunction "2_2") (pintype "passive"))
    )
    (net (code "56") (name "Net-(M1-G)") (class "Default")
      (node (ref "C11") (pin "1") (pinfunction "1_1") (pintype "passive"))
      (node (ref "D3") (pin "A") (pinfunction "A_A") (pintype "passive"))
      (node (ref "M1") (pin "2") (pinfunction "G_2") (pintype "passive"))
      (node (ref "R1") (pin "1") (pinfunction "1_1") (pintype "passive"))
    )
    (net (code "57") (name "Net-(M3-G)") (class "Default")
      (node (ref "M3") (pin "2") (pinfunction "G_2") (pintype "passive"))
      (node (ref "M4") (pin "3") (pinfunction "D_3") (pintype "passive"))
      (node (ref "R3") (pin "1") (pinfunction "1_1") (pintype "passive"))
    )
    (net (code "58") (name "Net-(Q2-B)") (class "Default")
      (node (ref "Q2") (pin "2") (pinfunction "B_2") (pintype "passive"))
      (node (ref "R27") (pin "1") (pinfunction "1_1") (pintype "passive"))
    )
    (net (code "59") (name "Net-(Q2-C)") (class "Default")
      (node (ref "D100") (pin "C") (pinfunction "C_C") (pintype "passive"))
      (node (ref "JP3") (pin "2") (pinfunction "2_2") (pintype "passive"))
      (node (ref "JP4") (pin "2") (pinfunction "2_2") (pintype "passive"))
      (node (ref "Q1") (pin "C") (pinfunction "C_C") (pintype "passive"))
      (node (ref "Q2") (pin "1") (pinfunction "C_1") (pintype "passive"))
      (node (ref "R5") (pin "2") (pinfunction "2_2") (pintype "passive"))
    )
    (net (code "60") (name "Net-(Q2-E)") (class "Default")
      (node (ref "Q1") (pin "B") (pinfunction "B_B") (pintype "passive"))
      (node (ref "Q2") (pin "3") (pinfunction "E_3") (pintype "passive"))
      (node (ref "R25") (pin "1") (pinfunction "1_1") (pintype "passive"))
    )
    (net (code "61") (name "Net-(Q3-B)") (class "Default")
      (node (ref "Q3") (pin "2") (pinfunction "B_2") (pintype "passive"))
      (node (ref "R34") (pin "1") (pinfunction "1_1") (pintype "passive"))
      (node (ref "R39") (pin "1") (pinfunction "1_1") (pintype "passive"))
      (node (ref "R50") (pin "1") (pinfunction "1_1") (pintype "passive"))
    )
    (net (code "62") (name "Net-(R18-Pad1)") (class "Default")
      (node (ref "R18") (pin "1") (pinfunction "1_1") (pintype "passive"))
      (node (ref "R19") (pin "2") (pinfunction "2_2") (pintype "passive"))
    )
    (net (code "63") (name "Net-(R21-Pad1)") (class "Default")
      (node (ref "R21") (pin "1") (pinfunction "1_1") (pintype "passive"))
      (node (ref "R22") (pin "2") (pinfunction "2_2") (pintype "passive"))
    )
    (net (code "64") (name "Net-(U$1-D2{slash}INT0)") (class "Default")
      (node (ref "D8") (pin "A") (pinfunction "A_A") (pintype "passive"))
      (node (ref "U$1") (pin "D2") (pinfunction "D2/INT0_D2") (pintype "bidirectional"))
    )
    (net (code "65") (name "unconnected-(HS1-K-PadK1)") (class "Default")
      (node (ref "HS1") (pin "K1") (pinfunction "K_K1") (pintype "passive"))
    )
    (net (code "66") (name "unconnected-(S2-P1-Pad2)") (class "Default")
      (node (ref "S2") (pin "2") (pinfunction "P1_2") (pintype "passive"))
    )
    (net (code "67") (name "unconnected-(S2-S1-Pad4)") (class "Default")
      (node (ref "S2") (pin "4") (pinfunction "S1_4") (pintype "passive"))
    )
    (net (code "68") (name "unconnected-(U$1-Pad3.3V)") (class "Default")
      (node (ref "U$1") (pin "3.3V") (pinfunction "3.3V_3.3V") (pintype "bidirectional"))
    )
    (net (code "69") (name "unconnected-(U$1-PadICSP1)") (class "Default")
      (node (ref "U$1") (pin "ICSP1") (pinfunction "ICSP1_ICSP1") (pintype "bidirectional"))
    )
    (net (code "70") (name "unconnected-(U$1-PadICSP2)") (class "Default")
      (node (ref "U$1") (pin "ICSP2") (pinfunction "ICSP2_ICSP2") (pintype "bidirectional"))
    )
    (net (code "71") (name "unconnected-(U$1-PadICSP3)") (class "Default")
      (node (ref "U$1") (pin "ICSP3") (pinfunction "ICSP3_ICSP3") (pintype "bidirectional"))
    )
    (net (code "72") (name "unconnected-(U$1-PadICSP4)") (class "Default")
      (node (ref "U$1") (pin "ICSP4") (pinfunction "ICSP4_ICSP4") (pintype "bidirectional"))
    )
    (net (code "73") (name "unconnected-(U$1-PadICSP5)") (class "Default")
      (node (ref "U$1") (pin "ICSP5") (pinfunction "ICSP5_ICSP5") (pintype "bidirectional"))
    )
    (net (code "74") (name "unconnected-(U$1-PadICSP6)") (class "Default")
      (node (ref "U$1") (pin "ICSP6") (pinfunction "ICSP6_ICSP6") (pintype "bidirectional"))
    )
    (net (code "75") (name "unconnected-(U$1-PadRST)") (class "Default")
      (node (ref "U$1") (pin "RST") (pinfunction "RST_RST") (pintype "bidirectional"))
    )
    (net (code "76") (name "unconnected-(U$1-PadRST1)") (class "Default")
      (node (ref "U$1") (pin "RST1") (pinfunction "RST1_RST1") (pintype "bidirectional"))
    )
    (net (code "77") (name "unconnected-(U$1-PadRX1)") (class "Default")
      (node (ref "U$1") (pin "RX1") (pinfunction "RX1_RX1") (pintype "bidirectional"))
    )
    (net (code "78") (name "unconnected-(U$1-PadTX0)") (class "Default")
      (node (ref "U$1") (pin "TX0") (pinfunction "TX0_TX0") (pintype "bidirectional"))
    )
    (net (code "79") (name "unconnected-(U2-PadRST)") (class "Default")
      (node (ref "U2") (pin "RST") (pinfunction "RST_RST") (pintype "bidirectional"))
    )
  )
)
